# POWER.net
KiCad netlist of a schematic drawn in Altium Designer
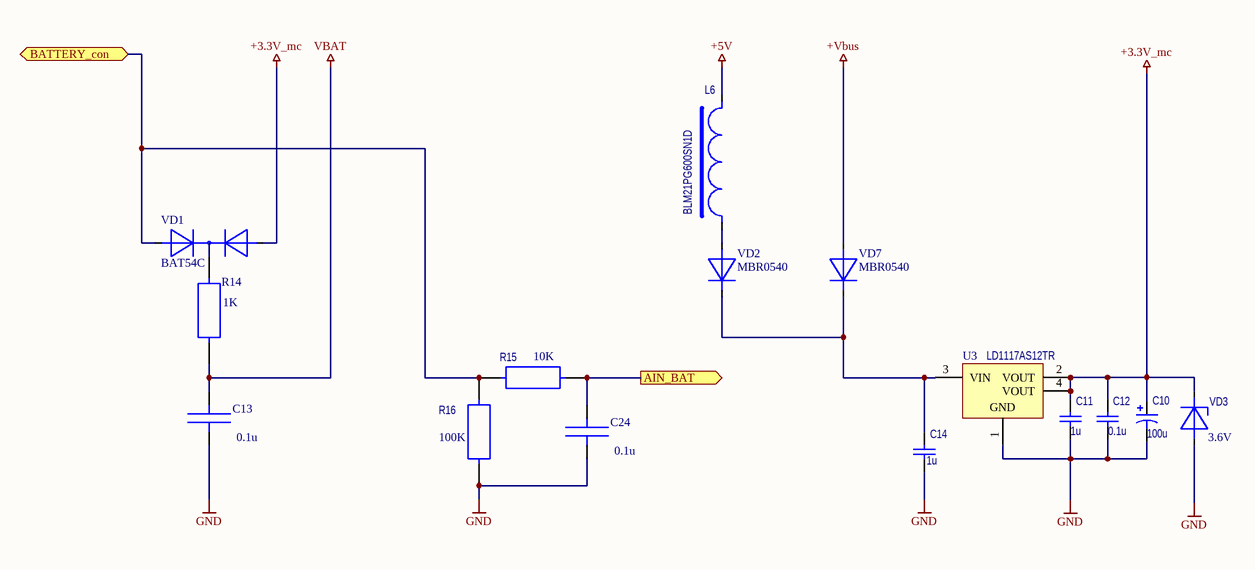
[diagram p0: POWER.SchDoc]

(export (version "E")
  (design (tool "Eeschema 10.0.6"))
  (components
    (comp (ref "C10")
      (value "100u")
      (footprint "CAP 5X...Х2")
      (description "Polarized Capacitor (Radial)")
      (fields (field (name "Comment") "100u 6.3V") (field (name "PUBLISHER") "Altium Limited"))
      (libsource (lib "Miscellaneous Devices") (part "Cap Pol1"))
    )
    (comp (ref "C11")
      (value "1u")
      (footprint "1206C")
      (description "Capacitor")
      (fields (field (name "PUBLISHER") "Altium Limited"))
      (libsource (lib "Miscellaneous Devices") (part "Cap"))
    )
    (comp (ref "C12")
      (value "0.1u")
      (footprint "0603C")
      (description "Capacitor")
      (fields (field (name "PUBLISHER") "Altium Limited"))
      (libsource (lib "Miscellaneous Devices") (part "Cap"))
    )
    (comp (ref "C13")
      (value "0.1u")
      (footprint "0603C")
      (description "Конденсатор обыкновенный")
      (libsource (lib "Основные") (part "CAP"))
    )
    (comp (ref "C14")
      (value "1u")
      (footprint "0603C")
      (description "Capacitor")
      (fields (field (name "PUBLISHER") "Altium Limited"))
      (libsource (lib "Miscellaneous Devices") (part "Cap"))
    )
    (comp (ref "C24")
      (value "0.1u")
      (footprint "0603C")
      (description "Конденсатор обыкновенный")
      (libsource (lib "Основные") (part "CAP"))
    )
    (comp (ref "L6")
      (value "BLM21PG600SN1D")
      (footprint "0805")
      (description "Индуктивность")
      (libsource (lib "Discrete") (part "INDUCTOR_"))
    )
    (comp (ref "R14")
      (value "1K")
      (footprint "0603R")
      (description "Резистор обыкновенный")
      (libsource (lib "Основные") (part "RES"))
    )
    (comp (ref "R15")
      (value "10K")
      (footprint "0603R")
      (description "Резистор обыкновенный")
      (libsource (lib "Discrete") (part "RES"))
    )
    (comp (ref "R16")
      (value "100K")
      (footprint "0603R")
      (description "Резистор обыкновенный")
      (libsource (lib "Discrete") (part "RES"))
    )
    (comp (ref "U3")
      (value "LD1117AS12TR")
      (footprint "SOT223")
      (description "1A, Low Drop Positive Voltage Regulator, 1.2V, 4-Pin SOT-223, Tape and Reel")
      (libsource (lib "STMicroelectronics Power Management Linear Regulator") (part "LD1117AS12TR"))
    )
    (comp (ref "VD1")
      (value "BAT54C")
      (footprint "SOT95P230X110-3L")
      (description "диодная сборка(общий катод)")
      (libsource (lib "Основные") (part "DIODE_PAIR_C"))
    )
    (comp (ref "VD2")
      (value "MBR0540")
      (footprint "SOD123")
      (description "Диод")
      (libsource (lib "Discrete") (part "DIODE"))
    )
    (comp (ref "VD3")
      (value "3.6V")
      (footprint "SOT23_1DIODE")
      (description "Стабилитрон")
      (fields (field (name "Comment") "BZX84C3V6"))
      (libsource (lib "Discrete") (part "ZENNER"))
    )
    (comp (ref "VD7")
      (value "MBR0540")
      (footprint "SOD123")
      (description "Диод")
      (libsource (lib "Discrete") (part "DIODE"))
    )
  )
  (nets
    (net (code "1") (name "+3.3V_mc") (class "Default")
      (node (ref "C10") (pin "1") (pinfunction "1_1") (pintype "passive"))
      (node (ref "C11") (pin "2") (pinfunction "2_2") (pintype "passive"))
      (node (ref "C12") (pin "2") (pinfunction "2_2") (pintype "passive"))
      (node (ref "U3") (pin "2") (pinfunction "VOUT_2") (pintype "power_in"))
      (node (ref "U3") (pin "4") (pinfunction "VOUT_4") (pintype "power_in"))
      (node (ref "VD1") (pin "1") (pinfunction "A1_1") (pintype "passive"))
      (node (ref "VD3") (pin "K") (pinfunction "K_K") (pintype "passive"))
    )
    (net (code "2") (name "+5V") (class "Default")
      (node (ref "L6") (pin "2") (pinfunction "2_2") (pintype "passive"))
    )
    (net (code "3") (name "+Vbus") (class "Default")
      (node (ref "VD7") (pin "A") (pinfunction "A_A") (pintype "passive"))
    )
    (net (code "4") (name "/AIN_BAT") (class "Default")
      (node (ref "C24") (pin "1") (pinfunction "1_1") (pintype "passive"))
      (node (ref "R15") (pin "1") (pinfunction "1_1") (pintype "passive"))
    )
    (net (code "5") (name "/BATTERY_con") (class "Default")
      (node (ref "R15") (pin "2") (pinfunction "2_2") (pintype "passive"))
      (node (ref "R16") (pin "2") (pinfunction "2_2") (pintype "passive"))
      (node (ref "VD1") (pin "2") (pinfunction "A2_2") (pintype "passive"))
    )
    (net (code "6") (name "GND") (class "Default")
      (node (ref "C10") (pin "2") (pinfunction "2_2") (pintype "passive"))
      (node (ref "C11") (pin "1") (pinfunction "1_1") (pintype "passive"))
      (node (ref "C12") (pin "1") (pinfunction "1_1") (pintype "passive"))
      (node (ref "C13") (pin "2") (pinfunction "2_2") (pintype "passive"))
      (node (ref "C14") (pin "1") (pinfunction "1_1") (pintype "passive"))
      (node (ref "C24") (pin "2") (pinfunction "2_2") (pintype "passive"))
      (node (ref "R16") (pin "1") (pinfunction "1_1") (pintype "passive"))
      (node (ref "U3") (pin "1") (pinfunction "GND_1") (pintype "power_in"))
      (node (ref "VD3") (pin "A") (pinfunction "A_A") (pintype "passive"))
    )
    (net (code "7") (name "Net-(L6-Pad1)") (class "Default")
      (node (ref "L6") (pin "1") (pinfunction "1_1") (pintype "passive"))
      (node (ref "VD2") (pin "A") (pinfunction "A_A") (pintype "passive"))
    )
    (net (code "8") (name "Net-(U3-VIN)") (class "Default")
      (node (ref "C14") (pin "2") (pinfunction "2_2") (pintype "passive"))
      (node (ref "U3") (pin "3") (pinfunction "VIN_3") (pintype "power_in"))
      (node (ref "VD2") (pin "K") (pinfunction "K_K") (pintype "passive"))
      (node (ref "VD7") (pin "K") (pinfunction "K_K") (pintype "passive"))
    )
    (net (code "9") (name "Net-(VD1-K)") (class "Default")
      (node (ref "R14") (pin "1") (pinfunction "1_1") (pintype "passive"))
      (node (ref "VD1") (pin "3") (pinfunction "K_3") (pintype "passive"))
    )
    (net (code "10") (name "VBAT") (class "Default")
      (node (ref "C13") (pin "1") (pinfunction "1_1") (pintype "passive"))
      (node (ref "R14") (pin "2") (pinfunction "2_2") (pintype "passive"))
    )
  )
)
